# BikeLightsESP32.net
KiCad netlist of a schematic drawn in EasyEDA
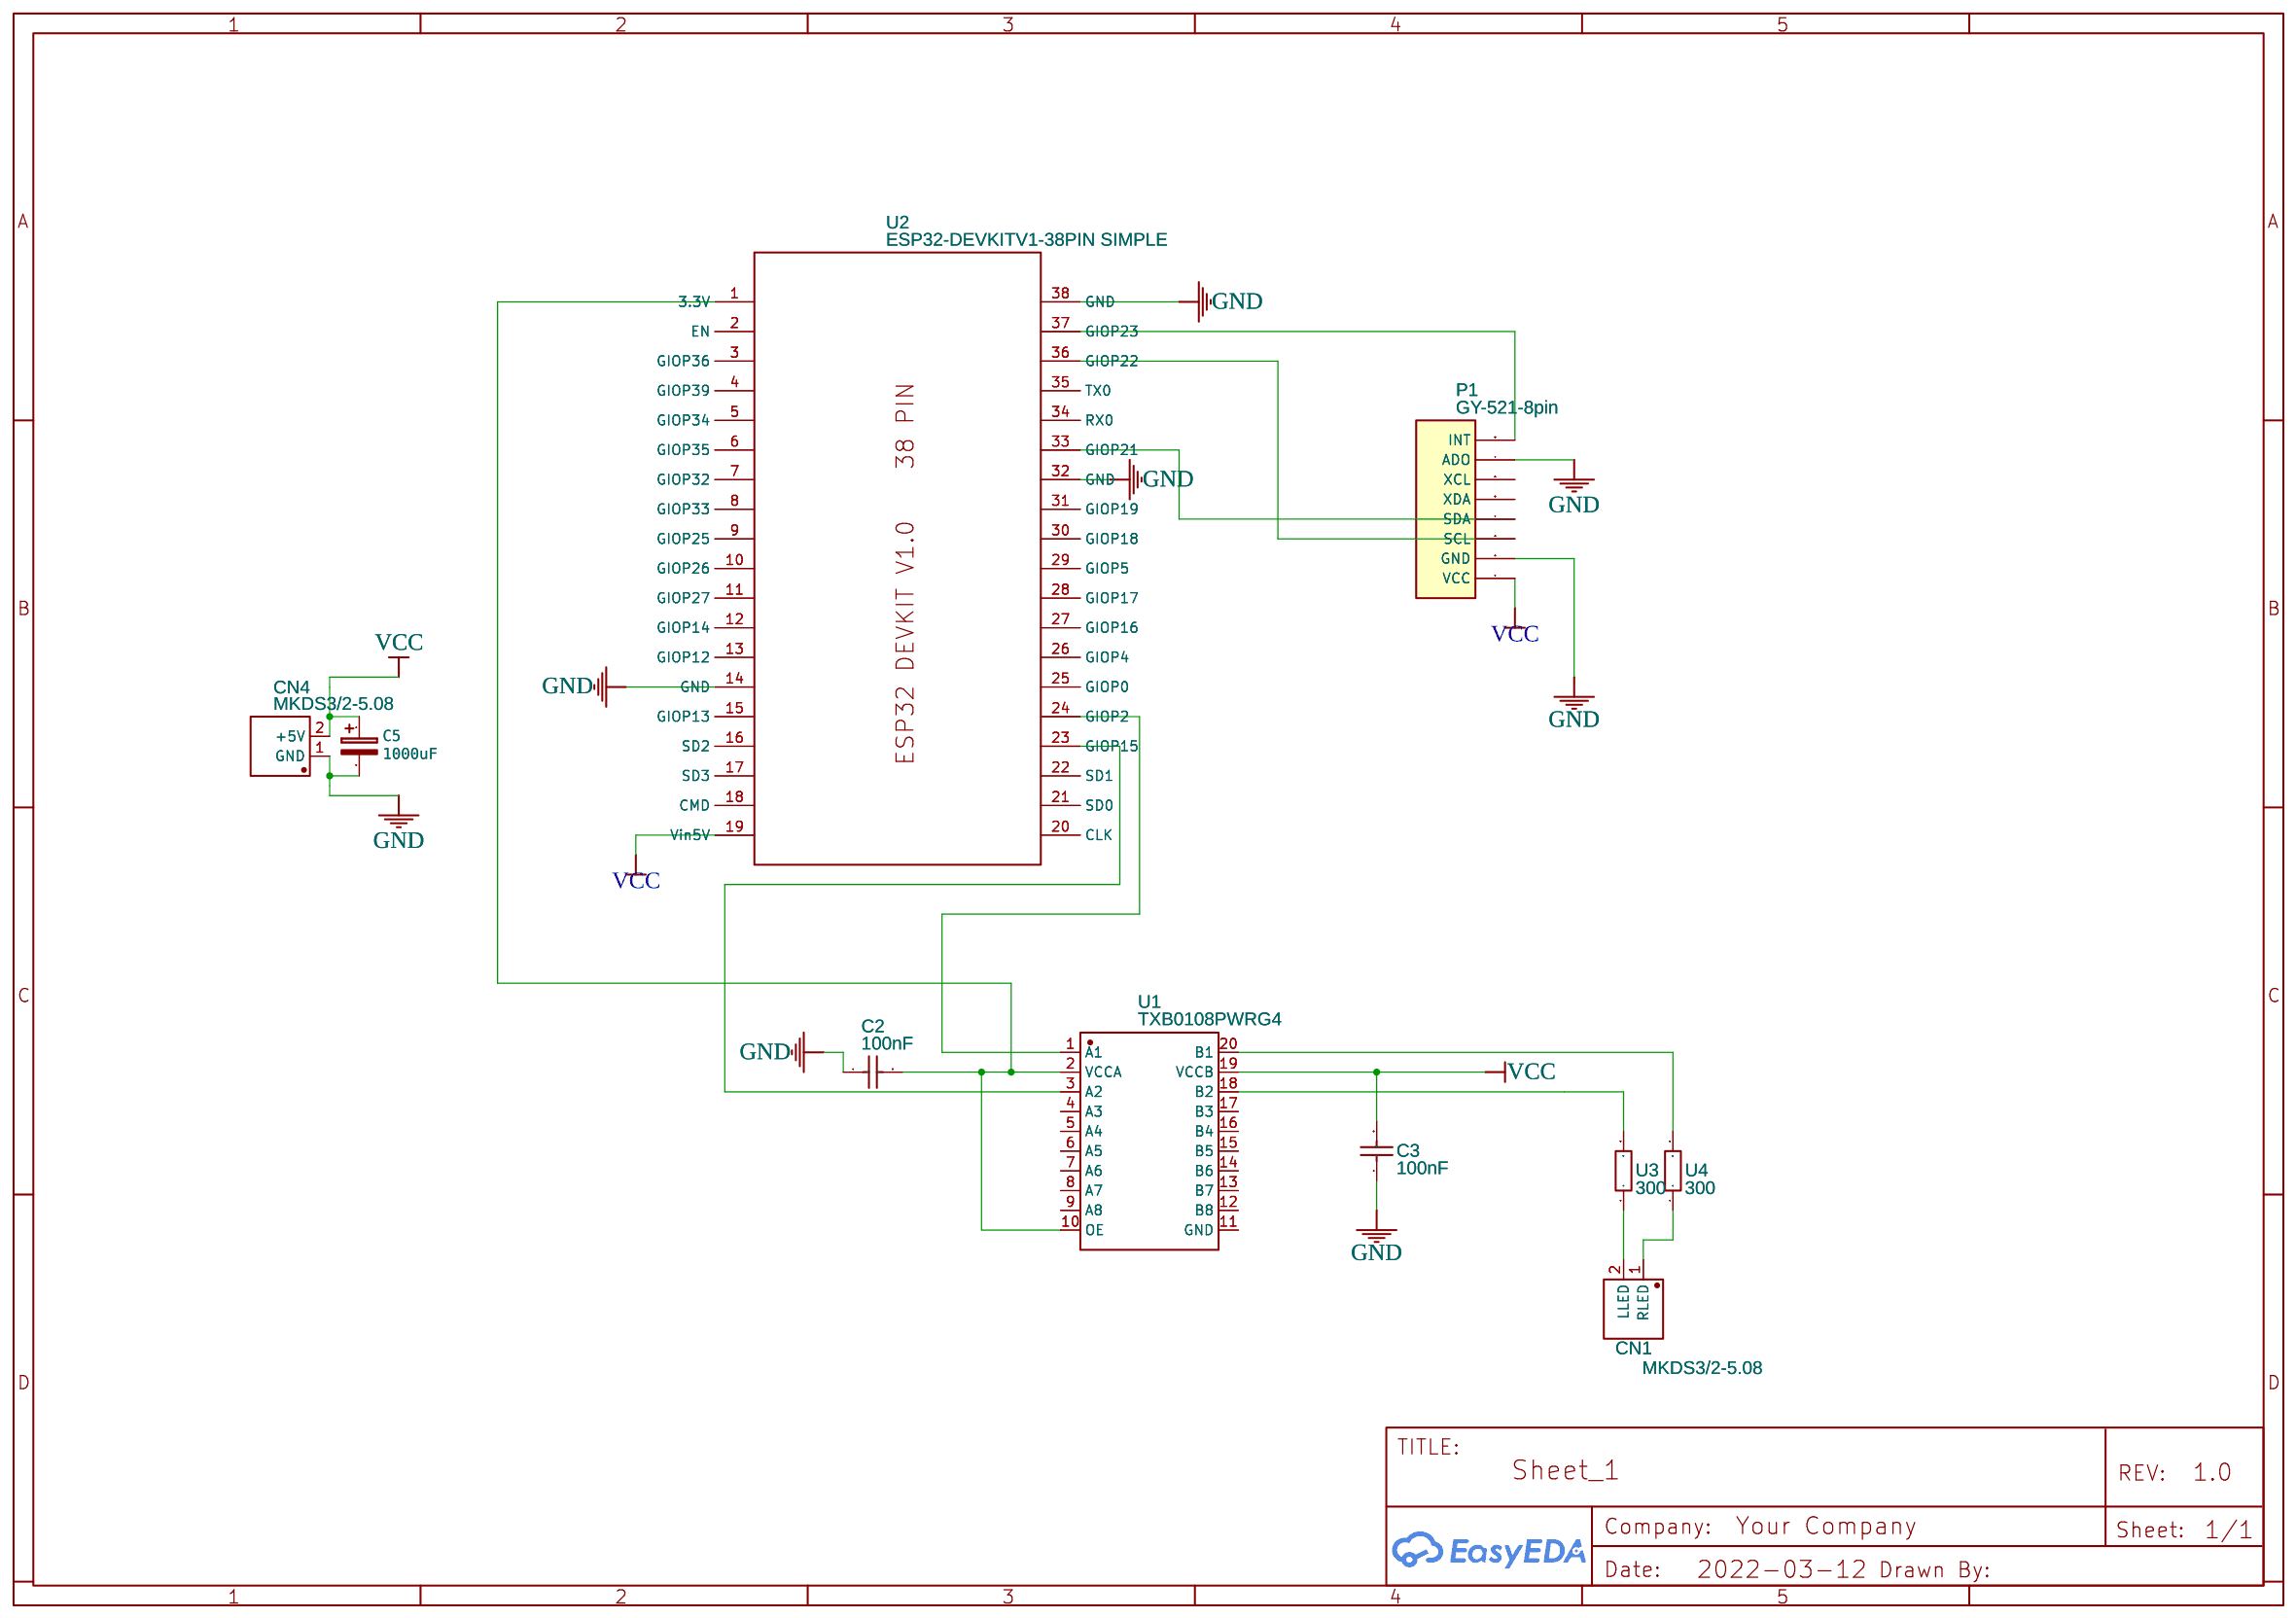
[diagram p0: schematic sheet]

(export (version "E")
  (design (tool "Eeschema 10.0.6"))
  (components
    (comp (ref "C2")
      (value "100nF")
      (fields
        (field (name "BOM_Manufacturer Part") "0805F104M500")
        (field (name "BOM_Supplier Part") "C95395")
      )
      (libsource (lib "") (part "0805F104M500"))
    )
    (comp (ref "C3")
      (value "100nF")
      (fields
        (field (name "BOM_Manufacturer Part") "0805F104M500")
        (field (name "BOM_Supplier Part") "C95395")
      )
      (libsource (lib "") (part "0805F104M500_1"))
    )
    (comp (ref "C5") (value "1000uF") (libsource (lib "") (part "Unknown_175_-435")))
    (comp (ref "CN1")
      (value "MKDS3/2-5.08")
      (fields (field (name "BOM_Supplier Part") "C89120"))
      (libsource (lib "") (part "MKDS3/2-5.08"))
    )
    (comp (ref "CN4")
      (value "MKDS3/2-5.08")
      (fields (field (name "BOM_Supplier Part") "C89120"))
      (libsource (lib "") (part "MKDS3/2-5.08_1"))
    )
    (comp (ref "P1") (value "GY-521-8pin") (libsource (lib "") (part "GY-521-8pin")))
    (comp (ref "U1")
      (value "TXB0108PWRG4")
      (fields (field (name "BOM_Supplier Part") "C2677607"))
      (libsource (lib "") (part "TXB0108PWRG4"))
    )
    (comp (ref "U2")
      (value "ESP32-DEVKITV1-38PIN SIMPLE")
      (fields (field (name "BOM_Manufacturer Part") "ESP-WROOM-32"))
      (libsource (lib "") (part "ESP32-DEVKITV1-38PIN SIMPLE"))
    )
    (comp (ref "U3")
      (value "300")
      (fields
        (field (name "BOM_Manufacturer Part") "HPCR0805F300RK9")
        (field (name "BOM_Supplier Part") "C365284")
      )
      (libsource (lib "") (part "HPCR0805F300RK9"))
    )
    (comp (ref "U4")
      (value "300")
      (fields
        (field (name "BOM_Manufacturer Part") "HPCR0805F300RK9")
        (field (name "BOM_Supplier Part") "C365284")
      )
      (libsource (lib "") (part "HPCR0805F300RK9"))
    )
  )
  (nets
    (net (code "1") (name "GND") (class "Default")
      (node (ref "C2") (pin "1") (pinfunction "1_1") (pintype "input"))
      (node (ref "C3") (pin "1") (pinfunction "1_1") (pintype "input"))
      (node (ref "C5") (pin "2") (pintype "unspecified"))
      (node (ref "CN4") (pin "1") (pinfunction "GND_1") (pintype "unspecified"))
      (node (ref "P1") (pin "2") (pinfunction "GND_2") (pintype "unspecified"))
      (node (ref "P1") (pin "7") (pinfunction "ADO_7") (pintype "unspecified"))
      (node (ref "U2") (pin "14") (pinfunction "GND_14") (pintype "unspecified"))
      (node (ref "U2") (pin "32") (pinfunction "GND_32") (pintype "unspecified"))
      (node (ref "U2") (pin "38") (pinfunction "GND_38") (pintype "unspecified"))
    )
    (net (code "2") (name "Net-(CN1-LLED)") (class "Default")
      (node (ref "CN1") (pin "2") (pinfunction "LLED_2") (pintype "unspecified"))
      (node (ref "U3") (pin "1") (pinfunction "1_1") (pintype "unspecified"))
    )
    (net (code "3") (name "Net-(CN1-RLED)") (class "Default")
      (node (ref "CN1") (pin "1") (pinfunction "RLED_1") (pintype "unspecified"))
      (node (ref "U4") (pin "1") (pinfunction "1_1") (pintype "unspecified"))
    )
    (net (code "4") (name "Net-(P1-INT)") (class "Default")
      (node (ref "P1") (pin "8") (pinfunction "INT_8") (pintype "unspecified"))
      (node (ref "U2") (pin "37") (pinfunction "GIOP23_37") (pintype "unspecified"))
    )
    (net (code "5") (name "Net-(P1-SCL)") (class "Default")
      (node (ref "P1") (pin "3") (pinfunction "SCL_3") (pintype "unspecified"))
      (node (ref "U2") (pin "36") (pinfunction "GIOP22_36") (pintype "unspecified"))
    )
    (net (code "6") (name "Net-(P1-SDA)") (class "Default")
      (node (ref "P1") (pin "4") (pinfunction "SDA_4") (pintype "unspecified"))
      (node (ref "U2") (pin "33") (pinfunction "GIOP21_33") (pintype "unspecified"))
    )
    (net (code "7") (name "Net-(U1-A1)") (class "Default")
      (node (ref "U1") (pin "1") (pinfunction "A1_1") (pintype "unspecified"))
      (node (ref "U2") (pin "24") (pinfunction "GIOP2_24") (pintype "unspecified"))
    )
    (net (code "8") (name "Net-(U1-A2)") (class "Default")
      (node (ref "U1") (pin "3") (pinfunction "A2_3") (pintype "unspecified"))
      (node (ref "U2") (pin "23") (pinfunction "GIOP15_23") (pintype "unspecified"))
    )
    (net (code "9") (name "Net-(U1-B1)") (class "Default")
      (node (ref "U1") (pin "20") (pinfunction "B1_20") (pintype "unspecified"))
      (node (ref "U4") (pin "2") (pinfunction "2_2") (pintype "unspecified"))
    )
    (net (code "10") (name "Net-(U1-B2)") (class "Default")
      (node (ref "U1") (pin "18") (pinfunction "B2_18") (pintype "unspecified"))
      (node (ref "U3") (pin "2") (pinfunction "2_2") (pintype "unspecified"))
    )
    (net (code "11") (name "Net-(U1-OE)") (class "Default")
      (node (ref "C2") (pin "2") (pinfunction "2_2") (pintype "input"))
      (node (ref "U1") (pin "10") (pinfunction "OE_10") (pintype "unspecified"))
      (node (ref "U1") (pin "2") (pinfunction "VCCA_2") (pintype "unspecified"))
      (node (ref "U2") (pin "1") (pinfunction "3.3V_1") (pintype "unspecified"))
    )
    (net (code "12") (name "VCC") (class "Default")
      (node (ref "C3") (pin "2") (pinfunction "2_2") (pintype "input"))
      (node (ref "C5") (pin "1") (pintype "unspecified"))
      (node (ref "CN4") (pin "2") (pinfunction "+5V_2") (pintype "unspecified"))
      (node (ref "P1") (pin "1") (pinfunction "VCC_1") (pintype "unspecified"))
      (node (ref "U1") (pin "19") (pinfunction "VCCB_19") (pintype "unspecified"))
      (node (ref "U2") (pin "19") (pinfunction "Vin5V_19") (pintype "unspecified"))
    )
    (net (code "13") (name "unconnected-(P1-XCL-Pad6)") (class "Default")
      (node (ref "P1") (pin "6") (pinfunction "XCL_6") (pintype "unspecified"))
    )
    (net (code "14") (name "unconnected-(P1-XDA-Pad5)") (class "Default")
      (node (ref "P1") (pin "5") (pinfunction "XDA_5") (pintype "unspecified"))
    )
    (net (code "15") (name "unconnected-(U1-A3-Pad4)") (class "Default")
      (node (ref "U1") (pin "4") (pinfunction "A3_4") (pintype "unspecified"))
    )
    (net (code "16") (name "unconnected-(U1-A4-Pad5)") (class "Default")
      (node (ref "U1") (pin "5") (pinfunction "A4_5") (pintype "unspecified"))
    )
    (net (code "17") (name "unconnected-(U1-A5-Pad6)") (class "Default")
      (node (ref "U1") (pin "6") (pinfunction "A5_6") (pintype "unspecified"))
    )
    (net (code "18") (name "unconnected-(U1-A6-Pad7)") (class "Default")
      (node (ref "U1") (pin "7") (pinfunction "A6_7") (pintype "unspecified"))
    )
    (net (code "19") (name "unconnected-(U1-A7-Pad8)") (class "Default")
      (node (ref "U1") (pin "8") (pinfunction "A7_8") (pintype "unspecified"))
    )
    (net (code "20") (name "unconnected-(U1-A8-Pad9)") (class "Default")
      (node (ref "U1") (pin "9") (pinfunction "A8_9") (pintype "unspecified"))
    )
    (net (code "21") (name "unconnected-(U1-B3-Pad17)") (class "Default")
      (node (ref "U1") (pin "17") (pinfunction "B3_17") (pintype "unspecified"))
    )
    (net (code "22") (name "unconnected-(U1-B4-Pad16)") (class "Default")
      (node (ref "U1") (pin "16") (pinfunction "B4_16") (pintype "unspecified"))
    )
    (net (code "23") (name "unconnected-(U1-B5-Pad15)") (class "Default")
      (node (ref "U1") (pin "15") (pinfunction "B5_15") (pintype "unspecified"))
    )
    (net (code "24") (name "unconnected-(U1-B6-Pad14)") (class "Default")
      (node (ref "U1") (pin "14") (pinfunction "B6_14") (pintype "unspecified"))
    )
    (net (code "25") (name "unconnected-(U1-B7-Pad13)") (class "Default")
      (node (ref "U1") (pin "13") (pinfunction "B7_13") (pintype "unspecified"))
    )
    (net (code "26") (name "unconnected-(U1-B8-Pad12)") (class "Default")
      (node (ref "U1") (pin "12") (pinfunction "B8_12") (pintype "unspecified"))
    )
    (net (code "27") (name "unconnected-(U1-GND-Pad11)") (class "Default")
      (node (ref "U1") (pin "11") (pinfunction "GND_11") (pintype "unspecified"))
    )
    (net (code "28") (name "unconnected-(U2-CLK-Pad20)") (class "Default")
      (node (ref "U2") (pin "20") (pinfunction "CLK_20") (pintype "unspecified"))
    )
    (net (code "29") (name "unconnected-(U2-CMD-Pad18)") (class "Default")
      (node (ref "U2") (pin "18") (pinfunction "CMD_18") (pintype "unspecified"))
    )
    (net (code "30") (name "unconnected-(U2-EN-Pad2)") (class "Default")
      (node (ref "U2") (pin "2") (pinfunction "EN_2") (pintype "unspecified"))
    )
    (net (code "31") (name "unconnected-(U2-GIOP0-Pad25)") (class "Default")
      (node (ref "U2") (pin "25") (pinfunction "GIOP0_25") (pintype "unspecified"))
    )
    (net (code "32") (name "unconnected-(U2-GIOP4-Pad26)") (class "Default")
      (node (ref "U2") (pin "26") (pinfunction "GIOP4_26") (pintype "unspecified"))
    )
    (net (code "33") (name "unconnected-(U2-GIOP5-Pad29)") (class "Default")
      (node (ref "U2") (pin "29") (pinfunction "GIOP5_29") (pintype "unspecified"))
    )
    (net (code "34") (name "unconnected-(U2-GIOP12-Pad13)") (class "Default")
      (node (ref "U2") (pin "13") (pinfunction "GIOP12_13") (pintype "unspecified"))
    )
    (net (code "35") (name "unconnected-(U2-GIOP13-Pad15)") (class "Default")
      (node (ref "U2") (pin "15") (pinfunction "GIOP13_15") (pintype "unspecified"))
    )
    (net (code "36") (name "unconnected-(U2-GIOP14-Pad12)") (class "Default")
      (node (ref "U2") (pin "12") (pinfunction "GIOP14_12") (pintype "unspecified"))
    )
    (net (code "37") (name "unconnected-(U2-GIOP16-Pad27)") (class "Default")
      (node (ref "U2") (pin "27") (pinfunction "GIOP16_27") (pintype "unspecified"))
    )
    (net (code "38") (name "unconnected-(U2-GIOP17-Pad28)") (class "Default")
      (node (ref "U2") (pin "28") (pinfunction "GIOP17_28") (pintype "unspecified"))
    )
    (net (code "39") (name "unconnected-(U2-GIOP18-Pad30)") (class "Default")
      (node (ref "U2") (pin "30") (pinfunction "GIOP18_30") (pintype "unspecified"))
    )
    (net (code "40") (name "unconnected-(U2-GIOP19-Pad31)") (class "Default")
      (node (ref "U2") (pin "31") (pinfunction "GIOP19_31") (pintype "unspecified"))
    )
    (net (code "41") (name "unconnected-(U2-GIOP25-Pad9)") (class "Default")
      (node (ref "U2") (pin "9") (pinfunction "GIOP25_9") (pintype "unspecified"))
    )
    (net (code "42") (name "unconnected-(U2-GIOP26-Pad10)") (class "Default")
      (node (ref "U2") (pin "10") (pinfunction "GIOP26_10") (pintype "unspecified"))
    )
    (net (code "43") (name "unconnected-(U2-GIOP27-Pad11)") (class "Default")
      (node (ref "U2") (pin "11") (pinfunction "GIOP27_11") (pintype "unspecified"))
    )
    (net (code "44") (name "unconnected-(U2-GIOP32-Pad7)") (class "Default")
      (node (ref "U2") (pin "7") (pinfunction "GIOP32_7") (pintype "unspecified"))
    )
    (net (code "45") (name "unconnected-(U2-GIOP33-Pad8)") (class "Default")
      (node (ref "U2") (pin "8") (pinfunction "GIOP33_8") (pintype "unspecified"))
    )
    (net (code "46") (name "unconnected-(U2-GIOP34-Pad5)") (class "Default")
      (node (ref "U2") (pin "5") (pinfunction "GIOP34_5") (pintype "unspecified"))
    )
    (net (code "47") (name "unconnected-(U2-GIOP35-Pad6)") (class "Default")
      (node (ref "U2") (pin "6") (pinfunction "GIOP35_6") (pintype "unspecified"))
    )
    (net (code "48") (name "unconnected-(U2-GIOP36-Pad3)") (class "Default")
      (node (ref "U2") (pin "3") (pinfunction "GIOP36_3") (pintype "unspecified"))
    )
    (net (code "49") (name "unconnected-(U2-GIOP39-Pad4)") (class "Default")
      (node (ref "U2") (pin "4") (pinfunction "GIOP39_4") (pintype "unspecified"))
    )
    (net (code "50") (name "unconnected-(U2-RX0-Pad34)") (class "Default")
      (node (ref "U2") (pin "34") (pinfunction "RX0_34") (pintype "unspecified"))
    )
    (net (code "51") (name "unconnected-(U2-SD0-Pad21)") (class "Default")
      (node (ref "U2") (pin "21") (pinfunction "SD0_21") (pintype "unspecified"))
    )
    (net (code "52") (name "unconnected-(U2-SD1-Pad22)") (class "Default")
      (node (ref "U2") (pin "22") (pinfunction "SD1_22") (pintype "unspecified"))
    )
    (net (code "53") (name "unconnected-(U2-SD2-Pad16)") (class "Default")
      (node (ref "U2") (pin "16") (pinfunction "SD2_16") (pintype "unspecified"))
    )
    (net (code "54") (name "unconnected-(U2-SD3-Pad17)") (class "Default")
      (node (ref "U2") (pin "17") (pinfunction "SD3_17") (pintype "unspecified"))
    )
    (net (code "55") (name "unconnected-(U2-TX0-Pad35)") (class "Default")
      (node (ref "U2") (pin "35") (pinfunction "TX0_35") (pintype "unspecified"))
    )
  )
)
